# Bv_Switch.net
KiCad netlist of a schematic drawn in EAGLE
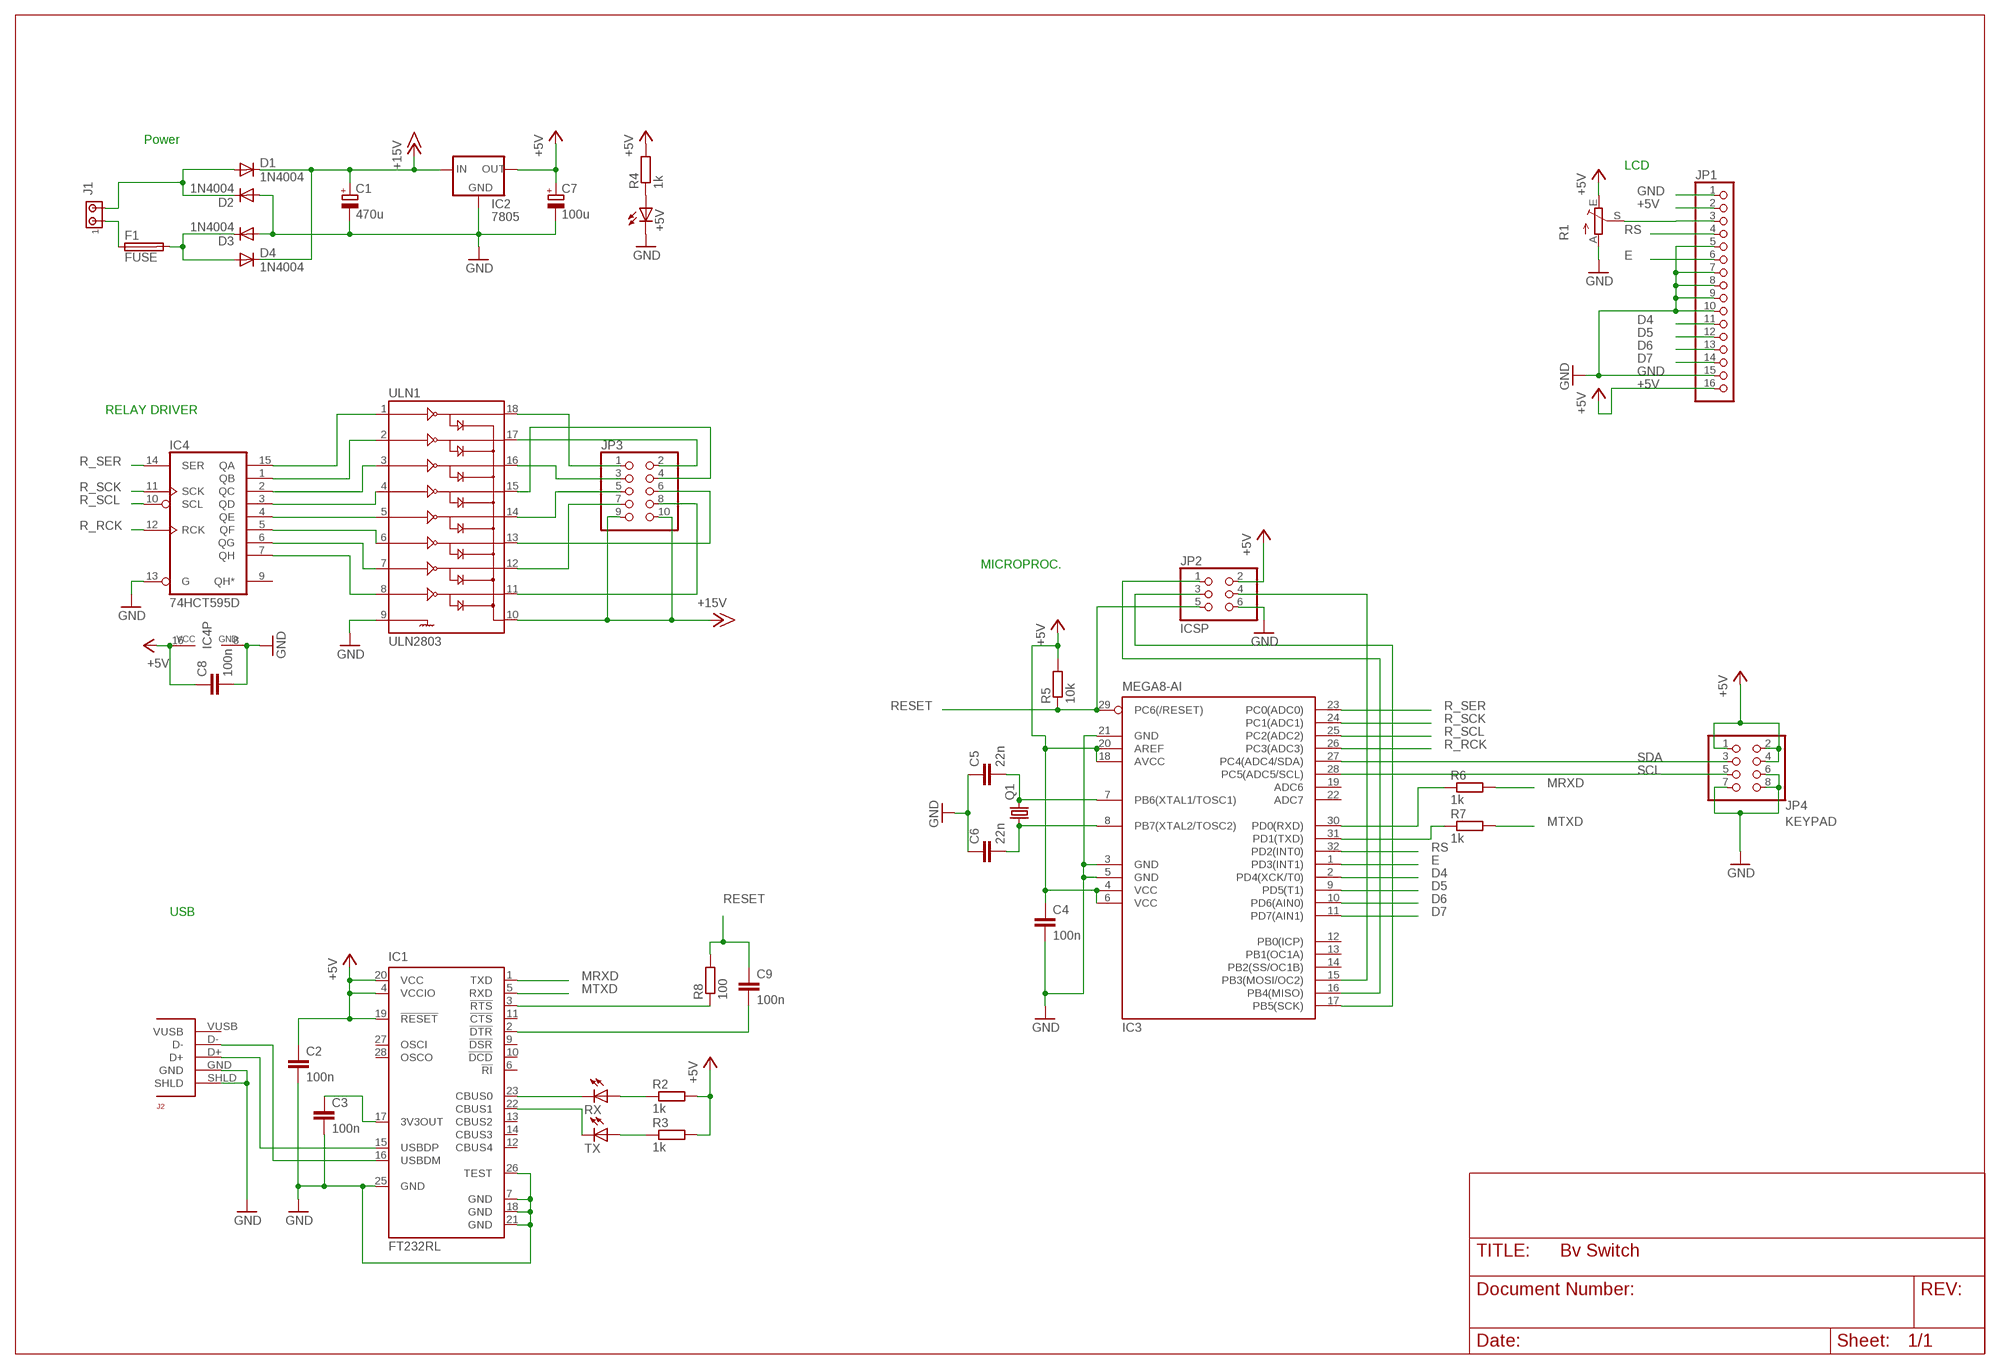
[diagram p0: schematic, sheet 1]

(export (version "E")
  (design (tool "Eeschema 10.0.6"))
  (components
    (comp (ref "+5V")
      (value "LEDCHIPLED_1206")
      (footprint "eagle-import:CHIPLED_1206")
      (libsource (lib "eagle-import") (part "LEDCHIPLED_1206"))
    )
    (comp (ref "C1")
      (value "470u")
      (footprint "eagle-import:153CLV-1010")
      (libsource (lib "eagle-import") (part "CPOL-EU153CLV-1010"))
    )
    (comp (ref "C2")
      (value "100n")
      (footprint "eagle-import:C1206")
      (libsource (lib "eagle-import") (part "C-EUC1206"))
    )
    (comp (ref "C3")
      (value "100n")
      (footprint "eagle-import:C1206")
      (libsource (lib "eagle-import") (part "C-EUC1206"))
    )
    (comp (ref "C4")
      (value "100n")
      (footprint "eagle-import:C1206")
      (libsource (lib "eagle-import") (part "C-EUC1206"))
    )
    (comp (ref "C5")
      (value "22n")
      (footprint "eagle-import:C1206")
      (libsource (lib "eagle-import") (part "C-EUC1206"))
    )
    (comp (ref "C6")
      (value "22n")
      (footprint "eagle-import:C1206")
      (libsource (lib "eagle-import") (part "C-EUC1206"))
    )
    (comp (ref "C7")
      (value "100u")
      (footprint "eagle-import:153CLV-1010")
      (libsource (lib "eagle-import") (part "CPOL-EU153CLV-1010"))
    )
    (comp (ref "C8")
      (value "100n")
      (footprint "eagle-import:C1206")
      (libsource (lib "eagle-import") (part "C-EUC1206"))
    )
    (comp (ref "C9")
      (value "100n")
      (footprint "eagle-import:C1206")
      (libsource (lib "eagle-import") (part "C-EUC1206"))
    )
    (comp (ref "D1")
      (value "1N4004")
      (footprint "eagle-import:DO41-10")
      (libsource (lib "eagle-import") (part "1N4004"))
    )
    (comp (ref "D2")
      (value "1N4004")
      (footprint "eagle-import:DO41-10")
      (libsource (lib "eagle-import") (part "1N4004"))
    )
    (comp (ref "D3")
      (value "1N4004")
      (footprint "eagle-import:DO41-10")
      (libsource (lib "eagle-import") (part "1N4004"))
    )
    (comp (ref "D4")
      (value "1N4004")
      (footprint "eagle-import:DO41-10")
      (libsource (lib "eagle-import") (part "1N4004"))
    )
    (comp (ref "F1")
      (value "FUSE")
      (footprint "eagle-import:FUSE_HOLDER_5X20MM")
      (libsource (lib "eagle-import") (part "FUSEBLANK_5X20MM"))
    )
    (comp (ref "IC1")
      (value "FT232RL")
      (footprint "eagle-import:SSOP28")
      (libsource (lib "eagle-import") (part "FT232RL"))
    )
    (comp (ref "IC2")
      (value "7805")
      (footprint "eagle-import:78XXL")
      (libsource (lib "eagle-import") (part "78XXL"))
    )
    (comp (ref "IC3")
      (value "MEGA8-AI")
      (footprint "eagle-import:TQFP32-08")
      (fields (field (name "MPN") "ATMEGA8-16AU"))
      (libsource (lib "eagle-import") (part "MEGA8-AI"))
    )
    (comp (ref "IC4")
      (value "74HCT595D")
      (footprint "eagle-import:SO16")
      (libsource (lib "eagle-import") (part "74595DHCT"))
    )
    (comp (ref "J1")
      (value "MTA02-156")
      (footprint "eagle-import:1X2MTA")
      (libsource (lib "eagle-import") (part "MTA02-156"))
    )
    (comp (ref "J2")
      (value "USBHD")
      (footprint "eagle-import:PINHD4")
      (libsource (lib "eagle-import") (part "USBHD"))
    )
    (comp (ref "JP1")
      (value "PINHD-1X16")
      (footprint "eagle-import:1X16")
      (libsource (lib "eagle-import") (part "PINHD-1X16"))
    )
    (comp (ref "JP2")
      (value "ICSP")
      (footprint "eagle-import:2X03")
      (libsource (lib "eagle-import") (part "PINHD-2X3"))
    )
    (comp (ref "JP3")
      (value "PINHD-2X5")
      (footprint "eagle-import:2X05")
      (libsource (lib "eagle-import") (part "PINHD-2X5"))
    )
    (comp (ref "JP4")
      (value "KEYPAD")
      (footprint "eagle-import:2X04")
      (libsource (lib "eagle-import") (part "PINHD-2X4"))
    )
    (comp (ref "Q1")
      (value "CRYSTALSM49")
      (footprint "eagle-import:SM49")
      (libsource (lib "eagle-import") (part "CRYSTALSM49"))
    )
    (comp (ref "R1")
      (value "TRIM_EU-CA6V")
      (footprint "eagle-import:CA6V")
      (libsource (lib "eagle-import") (part "TRIM_EU-CA6V"))
    )
    (comp (ref "R2")
      (value "1k")
      (footprint "eagle-import:R1206")
      (libsource (lib "eagle-import") (part "R-EU_R1206"))
    )
    (comp (ref "R3")
      (value "1k")
      (footprint "eagle-import:R1206")
      (libsource (lib "eagle-import") (part "R-EU_R1206"))
    )
    (comp (ref "R4")
      (value "1k")
      (footprint "eagle-import:R1206")
      (libsource (lib "eagle-import") (part "R-EU_R1206"))
    )
    (comp (ref "R5")
      (value "10k")
      (footprint "eagle-import:R1206")
      (libsource (lib "eagle-import") (part "R-EU_R1206"))
    )
    (comp (ref "R6")
      (value "1k")
      (footprint "eagle-import:R1206")
      (libsource (lib "eagle-import") (part "R-EU_R1206"))
    )
    (comp (ref "R7")
      (value "1k")
      (footprint "eagle-import:R1206")
      (libsource (lib "eagle-import") (part "R-EU_R1206"))
    )
    (comp (ref "R8")
      (value "100")
      (footprint "eagle-import:R1206")
      (libsource (lib "eagle-import") (part "R-EU_R1206"))
    )
    (comp (ref "RX")
      (value "LEDCHIPLED_1206")
      (footprint "eagle-import:CHIPLED_1206")
      (libsource (lib "eagle-import") (part "LEDCHIPLED_1206"))
    )
    (comp (ref "TX")
      (value "LEDCHIPLED_1206")
      (footprint "eagle-import:CHIPLED_1206")
      (libsource (lib "eagle-import") (part "LEDCHIPLED_1206"))
    )
    (comp (ref "ULN1")
      (value "ULN2803")
      (footprint "eagle-import:SO018")
      (libsource (lib "eagle-import") (part "ULN2803SOIC"))
    )
  )
  (nets
    (net (code "1") (name "+5V") (class "Default")
      (node (ref "C2") (pin "1") (pinfunction "1_1") (pintype "passive"))
      (node (ref "C4") (pin "1") (pinfunction "1_1") (pintype "passive"))
      (node (ref "C7") (pin "+") (pinfunction "+_+") (pintype "passive"))
      (node (ref "C8") (pin "1") (pinfunction "1_1") (pintype "passive"))
      (node (ref "IC1") (pin "19") (pinfunction "~{RESET}_19") (pintype "input"))
      (node (ref "IC1") (pin "20") (pinfunction "VCC_20") (pintype "power_in"))
      (node (ref "IC1") (pin "4") (pinfunction "VCCIO_4") (pintype "power_in"))
      (node (ref "IC2") (pin "OUT") (pinfunction "OUT_OUT") (pintype "passive"))
      (node (ref "IC3") (pin "18") (pinfunction "AVCC_18") (pintype "power_in"))
      (node (ref "IC3") (pin "20") (pinfunction "AREF_20") (pintype "passive"))
      (node (ref "IC3") (pin "4") (pinfunction "VCC_4") (pintype "power_in"))
      (node (ref "IC3") (pin "6") (pinfunction "VCC_6") (pintype "power_in"))
      (node (ref "IC4") (pin "16") (pinfunction "VCC_16") (pintype "power_in"))
      (node (ref "JP1") (pin "16") (pinfunction "16_16") (pintype "passive"))
      (node (ref "JP1") (pin "2") (pinfunction "2_2") (pintype "passive"))
      (node (ref "JP2") (pin "2") (pinfunction "2_2") (pintype "passive"))
      (node (ref "JP4") (pin "1") (pinfunction "1_1") (pintype "passive"))
      (node (ref "JP4") (pin "2") (pinfunction "2_2") (pintype "passive"))
      (node (ref "JP4") (pin "4") (pinfunction "4_4") (pintype "passive"))
      (node (ref "R1") (pin "E") (pinfunction "E_E") (pintype "passive"))
      (node (ref "R2") (pin "2") (pinfunction "2_2") (pintype "passive"))
      (node (ref "R3") (pin "2") (pinfunction "2_2") (pintype "passive"))
      (node (ref "R4") (pin "2") (pinfunction "2_2") (pintype "passive"))
      (node (ref "R5") (pin "2") (pinfunction "2_2") (pintype "passive"))
    )
    (net (code "2") (name "+15V") (class "Default")
      (node (ref "C1") (pin "+") (pinfunction "+_+") (pintype "passive"))
      (node (ref "D1") (pin "C") (pinfunction "C_C") (pintype "passive"))
      (node (ref "D4") (pin "C") (pinfunction "C_C") (pintype "passive"))
      (node (ref "IC2") (pin "IN") (pinfunction "IN_IN") (pintype "input"))
      (node (ref "JP3") (pin "10") (pinfunction "10_10") (pintype "passive"))
      (node (ref "JP3") (pin "9") (pinfunction "9_9") (pintype "passive"))
      (node (ref "ULN1") (pin "10") (pinfunction "10_10") (pintype "bidirectional"))
    )
    (net (code "3") (name "/D4") (class "Default")
      (node (ref "IC3") (pin "2") (pinfunction "PD4(XCK/T0)_2") (pintype "bidirectional"))
      (node (ref "JP1") (pin "11") (pinfunction "11_11") (pintype "passive"))
    )
    (net (code "4") (name "/D5") (class "Default")
      (node (ref "IC3") (pin "9") (pinfunction "PD5(T1)_9") (pintype "bidirectional"))
      (node (ref "JP1") (pin "12") (pinfunction "12_12") (pintype "passive"))
    )
    (net (code "5") (name "/D6") (class "Default")
      (node (ref "IC3") (pin "10") (pinfunction "PD6(AIN0)_10") (pintype "bidirectional"))
      (node (ref "JP1") (pin "13") (pinfunction "13_13") (pintype "passive"))
    )
    (net (code "6") (name "/D7") (class "Default")
      (node (ref "IC3") (pin "11") (pinfunction "PD7(AIN1)_11") (pintype "bidirectional"))
      (node (ref "JP1") (pin "14") (pinfunction "14_14") (pintype "passive"))
    )
    (net (code "7") (name "/E") (class "Default")
      (node (ref "IC3") (pin "1") (pinfunction "PD3(INT1)_1") (pintype "bidirectional"))
      (node (ref "JP1") (pin "6") (pinfunction "6_6") (pintype "passive"))
    )
    (net (code "8") (name "/MRXD") (class "Default")
      (node (ref "IC1") (pin "1") (pinfunction "TXD_1") (pintype "output"))
      (node (ref "R6") (pin "2") (pinfunction "2_2") (pintype "passive"))
    )
    (net (code "9") (name "/MTXD") (class "Default")
      (node (ref "IC1") (pin "5") (pinfunction "RXD_5") (pintype "input"))
      (node (ref "R7") (pin "2") (pinfunction "2_2") (pintype "passive"))
    )
    (net (code "10") (name "/RESET") (class "Default")
      (node (ref "C9") (pin "1") (pinfunction "1_1") (pintype "passive"))
      (node (ref "IC3") (pin "29") (pinfunction "PC6(/RESET)_29") (pintype "bidirectional"))
      (node (ref "JP2") (pin "5") (pinfunction "5_5") (pintype "passive"))
      (node (ref "R5") (pin "1") (pinfunction "1_1") (pintype "passive"))
      (node (ref "R8") (pin "2") (pinfunction "2_2") (pintype "passive"))
    )
    (net (code "11") (name "/RS") (class "Default")
      (node (ref "IC3") (pin "32") (pinfunction "PD2(INT0)_32") (pintype "bidirectional"))
      (node (ref "JP1") (pin "4") (pinfunction "4_4") (pintype "passive"))
    )
    (net (code "12") (name "/R_RCK") (class "Default")
      (node (ref "IC3") (pin "26") (pinfunction "PC3(ADC3)_26") (pintype "bidirectional"))
      (node (ref "IC4") (pin "12") (pinfunction "RCK_12") (pintype "input"))
    )
    (net (code "13") (name "/R_SCK") (class "Default")
      (node (ref "IC3") (pin "24") (pinfunction "PC1(ADC1)_24") (pintype "bidirectional"))
      (node (ref "IC4") (pin "11") (pinfunction "SCK_11") (pintype "input"))
    )
    (net (code "14") (name "/R_SCL") (class "Default")
      (node (ref "IC3") (pin "25") (pinfunction "PC2(ADC2)_25") (pintype "bidirectional"))
      (node (ref "IC4") (pin "10") (pinfunction "SCL_10") (pintype "input"))
    )
    (net (code "15") (name "/R_SER") (class "Default")
      (node (ref "IC3") (pin "23") (pinfunction "PC0(ADC0)_23") (pintype "bidirectional"))
      (node (ref "IC4") (pin "14") (pinfunction "SER_14") (pintype "input"))
    )
    (net (code "16") (name "/SCL") (class "Default")
      (node (ref "IC3") (pin "28") (pinfunction "PC5(ADC5/SCL)_28") (pintype "bidirectional"))
      (node (ref "JP4") (pin "5") (pinfunction "5_5") (pintype "passive"))
    )
    (net (code "17") (name "/SDA") (class "Default")
      (node (ref "IC3") (pin "27") (pinfunction "PC4(ADC4/SDA)_27") (pintype "bidirectional"))
      (node (ref "JP4") (pin "3") (pinfunction "3_3") (pintype "passive"))
    )
    (net (code "18") (name "GND") (class "Default")
      (node (ref "+5V") (pin "C") (pinfunction "C_C") (pintype "passive"))
      (node (ref "C1") (pin "-") (pinfunction "-_-") (pintype "passive"))
      (node (ref "C2") (pin "2") (pinfunction "2_2") (pintype "passive"))
      (node (ref "C3") (pin "2") (pinfunction "2_2") (pintype "passive"))
      (node (ref "C4") (pin "2") (pinfunction "2_2") (pintype "passive"))
      (node (ref "C5") (pin "1") (pinfunction "1_1") (pintype "passive"))
      (node (ref "C6") (pin "1") (pinfunction "1_1") (pintype "passive"))
      (node (ref "C7") (pin "-") (pinfunction "-_-") (pintype "passive"))
      (node (ref "C8") (pin "2") (pinfunction "2_2") (pintype "passive"))
      (node (ref "D2") (pin "A") (pinfunction "A_A") (pintype "passive"))
      (node (ref "D3") (pin "A") (pinfunction "A_A") (pintype "passive"))
      (node (ref "IC1") (pin "18") (pinfunction "GND_18") (pintype "power_in"))
      (node (ref "IC1") (pin "21") (pinfunction "GND_21") (pintype "power_in"))
      (node (ref "IC1") (pin "25") (pinfunction "GND_25") (pintype "power_in"))
      (node (ref "IC1") (pin "26") (pinfunction "TEST_26") (pintype "input"))
      (node (ref "IC1") (pin "7") (pinfunction "GND_7") (pintype "power_in"))
      (node (ref "IC2") (pin "GND") (pinfunction "GND_GND") (pintype "input"))
      (node (ref "IC3") (pin "21") (pinfunction "GND_21") (pintype "power_in"))
      (node (ref "IC3") (pin "3") (pinfunction "GND_3") (pintype "power_in"))
      (node (ref "IC3") (pin "5") (pinfunction "GND_5") (pintype "power_in"))
      (node (ref "IC4") (pin "13") (pinfunction "G_13") (pintype "input"))
      (node (ref "IC4") (pin "8") (pinfunction "GND_8") (pintype "power_in"))
      (node (ref "J2") (pin "GND") (pinfunction "GND_GND") (pintype "bidirectional"))
      (node (ref "J2") (pin "SHLD") (pinfunction "SHLD_SHLD") (pintype "bidirectional"))
      (node (ref "JP1") (pin "1") (pinfunction "1_1") (pintype "passive"))
      (node (ref "JP1") (pin "10") (pinfunction "10_10") (pintype "passive"))
      (node (ref "JP1") (pin "15") (pinfunction "15_15") (pintype "passive"))
      (node (ref "JP1") (pin "5") (pinfunction "5_5") (pintype "passive"))
      (node (ref "JP1") (pin "7") (pinfunction "7_7") (pintype "passive"))
      (node (ref "JP1") (pin "8") (pinfunction "8_8") (pintype "passive"))
      (node (ref "JP1") (pin "9") (pinfunction "9_9") (pintype "passive"))
      (node (ref "JP2") (pin "6") (pinfunction "6_6") (pintype "passive"))
      (node (ref "JP4") (pin "6") (pinfunction "6_6") (pintype "passive"))
      (node (ref "JP4") (pin "7") (pinfunction "7_7") (pintype "passive"))
      (node (ref "JP4") (pin "8") (pinfunction "8_8") (pintype "passive"))
      (node (ref "R1") (pin "A") (pinfunction "A_A") (pintype "passive"))
      (node (ref "ULN1") (pin "9") (pinfunction "9_9") (pintype "bidirectional"))
    )
    (net (code "19") (name "Net-(+5V-PadA)") (class "Default")
      (node (ref "+5V") (pin "A") (pinfunction "A_A") (pintype "passive"))
      (node (ref "R4") (pin "1") (pinfunction "1_1") (pintype "passive"))
    )
    (net (code "20") (name "Net-(D1-PadA)") (class "Default")
      (node (ref "D1") (pin "A") (pinfunction "A_A") (pintype "passive"))
      (node (ref "D2") (pin "C") (pinfunction "C_C") (pintype "passive"))
      (node (ref "J1") (pin "2") (pinfunction "2_2") (pintype "passive"))
    )
    (net (code "21") (name "Net-(D3-PadC)") (class "Default")
      (node (ref "D3") (pin "C") (pinfunction "C_C") (pintype "passive"))
      (node (ref "D4") (pin "A") (pinfunction "A_A") (pintype "passive"))
      (node (ref "F1") (pin "2") (pinfunction "2_2") (pintype "passive"))
    )
    (net (code "22") (name "Net-(F1-Pad1)") (class "Default")
      (node (ref "F1") (pin "1") (pinfunction "1_1") (pintype "passive"))
      (node (ref "J1") (pin "1") (pinfunction "1_1") (pintype "passive"))
    )
    (net (code "23") (name "Net-(IC1-3V3OUT)") (class "Default")
      (node (ref "C3") (pin "1") (pinfunction "1_1") (pintype "passive"))
      (node (ref "IC1") (pin "17") (pinfunction "3V3OUT_17") (pintype "output"))
    )
    (net (code "24") (name "Net-(IC1-CBUS0)") (class "Default")
      (node (ref "IC1") (pin "23") (pinfunction "CBUS0_23") (pintype "bidirectional"))
      (node (ref "RX") (pin "C") (pinfunction "C_C") (pintype "passive"))
    )
    (net (code "25") (name "Net-(IC1-CBUS1)") (class "Default")
      (node (ref "IC1") (pin "22") (pinfunction "CBUS1_22") (pintype "bidirectional"))
      (node (ref "TX") (pin "C") (pinfunction "C_C") (pintype "passive"))
    )
    (net (code "26") (name "Net-(IC1-USBDM)") (class "Default")
      (node (ref "IC1") (pin "16") (pinfunction "USBDM_16") (pintype "bidirectional"))
      (node (ref "J2") (pin "D-") (pinfunction "D-_D-") (pintype "bidirectional"))
    )
    (net (code "27") (name "Net-(IC1-USBDP)") (class "Default")
      (node (ref "IC1") (pin "15") (pinfunction "USBDP_15") (pintype "bidirectional"))
      (node (ref "J2") (pin "D+") (pinfunction "D+_D+") (pintype "bidirectional"))
    )
    (net (code "28") (name "Net-(IC1-~{DTR})") (class "Default")
      (node (ref "C9") (pin "2") (pinfunction "2_2") (pintype "passive"))
      (node (ref "IC1") (pin "2") (pinfunction "~{DTR}_2") (pintype "output"))
    )
    (net (code "29") (name "Net-(IC1-~{RTS})") (class "Default")
      (node (ref "IC1") (pin "3") (pinfunction "~{RTS}_3") (pintype "output"))
      (node (ref "R8") (pin "1") (pinfunction "1_1") (pintype "passive"))
    )
    (net (code "30") (name "Net-(IC3-PB3(MOSI{slash}OC2))") (class "Default")
      (node (ref "IC3") (pin "15") (pinfunction "PB3(MOSI/OC2)_15") (pintype "bidirectional"))
      (node (ref "JP2") (pin "4") (pinfunction "4_4") (pintype "passive"))
    )
    (net (code "31") (name "Net-(IC3-PB4(MISO))") (class "Default")
      (node (ref "IC3") (pin "16") (pinfunction "PB4(MISO)_16") (pintype "bidirectional"))
      (node (ref "JP2") (pin "1") (pinfunction "1_1") (pintype "passive"))
    )
    (net (code "32") (name "Net-(IC3-PB5(SCK))") (class "Default")
      (node (ref "IC3") (pin "17") (pinfunction "PB5(SCK)_17") (pintype "bidirectional"))
      (node (ref "JP2") (pin "3") (pinfunction "3_3") (pintype "passive"))
    )
    (net (code "33") (name "Net-(IC3-PB6(XTAL1{slash}TOSC1))") (class "Default")
      (node (ref "C5") (pin "2") (pinfunction "2_2") (pintype "passive"))
      (node (ref "IC3") (pin "7") (pinfunction "PB6(XTAL1/TOSC1)_7") (pintype "bidirectional"))
      (node (ref "Q1") (pin "2") (pinfunction "2_2") (pintype "passive"))
    )
    (net (code "34") (name "Net-(IC3-PB7(XTAL2{slash}TOSC2))") (class "Default")
      (node (ref "C6") (pin "2") (pinfunction "2_2") (pintype "passive"))
      (node (ref "IC3") (pin "8") (pinfunction "PB7(XTAL2/TOSC2)_8") (pintype "bidirectional"))
      (node (ref "Q1") (pin "1") (pinfunction "1_1") (pintype "passive"))
    )
    (net (code "35") (name "Net-(IC3-PD0(RXD))") (class "Default")
      (node (ref "IC3") (pin "30") (pinfunction "PD0(RXD)_30") (pintype "bidirectional"))
      (node (ref "R6") (pin "1") (pinfunction "1_1") (pintype "passive"))
    )
    (net (code "36") (name "Net-(IC3-PD1(TXD))") (class "Default")
      (node (ref "IC3") (pin "31") (pinfunction "PD1(TXD)_31") (pintype "bidirectional"))
      (node (ref "R7") (pin "1") (pinfunction "1_1") (pintype "passive"))
    )
    (net (code "37") (name "Net-(IC4A-QA)") (class "Default")
      (node (ref "IC4") (pin "15") (pinfunction "QA_15") (pintype "tri_state"))
      (node (ref "ULN1") (pin "1") (pinfunction "1_1") (pintype "bidirectional"))
    )
    (net (code "38") (name "Net-(IC4A-QB)") (class "Default")
      (node (ref "IC4") (pin "1") (pinfunction "QB_1") (pintype "tri_state"))
      (node (ref "ULN1") (pin "2") (pinfunction "2_2") (pintype "bidirectional"))
    )
    (net (code "39") (name "Net-(IC4A-QC)") (class "Default")
      (node (ref "IC4") (pin "2") (pinfunction "QC_2") (pintype "tri_state"))
      (node (ref "ULN1") (pin "3") (pinfunction "3_3") (pintype "bidirectional"))
    )
    (net (code "40") (name "Net-(IC4A-QD)") (class "Default")
      (node (ref "IC4") (pin "3") (pinfunction "QD_3") (pintype "tri_state"))
      (node (ref "ULN1") (pin "4") (pinfunction "4_4") (pintype "bidirectional"))
    )
    (net (code "41") (name "Net-(IC4A-QE)") (class "Default")
      (node (ref "IC4") (pin "4") (pinfunction "QE_4") (pintype "tri_state"))
      (node (ref "ULN1") (pin "5") (pinfunction "5_5") (pintype "bidirectional"))
    )
    (net (code "42") (name "Net-(IC4A-QF)") (class "Default")
      (node (ref "IC4") (pin "5") (pinfunction "QF_5") (pintype "tri_state"))
      (node (ref "ULN1") (pin "6") (pinfunction "6_6") (pintype "bidirectional"))
    )
    (net (code "43") (name "Net-(IC4A-QG)") (class "Default")
      (node (ref "IC4") (pin "6") (pinfunction "QG_6") (pintype "tri_state"))
      (node (ref "ULN1") (pin "7") (pinfunction "7_7") (pintype "bidirectional"))
    )
    (net (code "44") (name "Net-(IC4A-QH)") (class "Default")
      (node (ref "IC4") (pin "7") (pinfunction "QH_7") (pintype "tri_state"))
      (node (ref "ULN1") (pin "8") (pinfunction "8_8") (pintype "bidirectional"))
    )
    (net (code "45") (name "Net-(JP1-Pad3)") (class "Default")
      (node (ref "JP1") (pin "3") (pinfunction "3_3") (pintype "passive"))
      (node (ref "R1") (pin "S") (pinfunction "S_S") (pintype "passive"))
    )
    (net (code "46") (name "Net-(JP3-Pad1)") (class "Default")
      (node (ref "JP3") (pin "1") (pinfunction "1_1") (pintype "passive"))
      (node (ref "ULN1") (pin "18") (pinfunction "18_18") (pintype "bidirectional"))
    )
    (net (code "47") (name "Net-(JP3-Pad2)") (class "Default")
      (node (ref "JP3") (pin "2") (pinfunction "2_2") (pintype "passive"))
      (node (ref "ULN1") (pin "17") (pinfunction "17_17") (pintype "bidirectional"))
    )
    (net (code "48") (name "Net-(JP3-Pad3)") (class "Default")
      (node (ref "JP3") (pin "3") (pinfunction "3_3") (pintype "passive"))
      (node (ref "ULN1") (pin "16") (pinfunction "16_16") (pintype "bidirectional"))
    )
    (net (code "49") (name "Net-(JP3-Pad4)") (class "Default")
      (node (ref "JP3") (pin "4") (pinfunction "4_4") (pintype "passive"))
      (node (ref "ULN1") (pin "15") (pinfunction "15_15") (pintype "bidirectional"))
    )
    (net (code "50") (name "Net-(JP3-Pad5)") (class "Default")
      (node (ref "JP3") (pin "5") (pinfunction "5_5") (pintype "passive"))
      (node (ref "ULN1") (pin "14") (pinfunction "14_14") (pintype "bidirectional"))
    )
    (net (code "51") (name "Net-(JP3-Pad6)") (class "Default")
      (node (ref "JP3") (pin "6") (pinfunction "6_6") (pintype "passive"))
      (node (ref "ULN1") (pin "13") (pinfunction "13_13") (pintype "bidirectional"))
    )
    (net (code "52") (name "Net-(JP3-Pad7)") (class "Default")
      (node (ref "JP3") (pin "7") (pinfunction "7_7") (pintype "passive"))
      (node (ref "ULN1") (pin "12") (pinfunction "12_12") (pintype "bidirectional"))
    )
    (net (code "53") (name "Net-(JP3-Pad8)") (class "Default")
      (node (ref "JP3") (pin "8") (pinfunction "8_8") (pintype "passive"))
      (node (ref "ULN1") (pin "11") (pinfunction "11_11") (pintype "bidirectional"))
    )
    (net (code "54") (name "Net-(R2-Pad1)") (class "Default")
      (node (ref "R2") (pin "1") (pinfunction "1_1") (pintype "passive"))
      (node (ref "RX") (pin "A") (pinfunction "A_A") (pintype "passive"))
    )
    (net (code "55") (name "Net-(R3-Pad1)") (class "Default")
      (node (ref "R3") (pin "1") (pinfunction "1_1") (pintype "passive"))
      (node (ref "TX") (pin "A") (pinfunction "A_A") (pintype "passive"))
    )
    (net (code "56") (name "unconnected-(IC1-CBUS2-Pad13)") (class "Default")
      (node (ref "IC1") (pin "13") (pinfunction "CBUS2_13") (pintype "bidirectional"))
    )
    (net (code "57") (name "unconnected-(IC1-CBUS3-Pad14)") (class "Default")
      (node (ref "IC1") (pin "14") (pinfunction "CBUS3_14") (pintype "bidirectional"))
    )
    (net (code "58") (name "unconnected-(IC1-CBUS4-Pad12)") (class "Default")
      (node (ref "IC1") (pin "12") (pinfunction "CBUS4_12") (pintype "bidirectional"))
    )
    (net (code "59") (name "unconnected-(IC1-OSCI-Pad27)") (class "Default")
      (node (ref "IC1") (pin "27") (pinfunction "OSCI_27") (pintype "input"))
    )
    (net (code "60") (name "unconnected-(IC1-OSCO-Pad28)") (class "Default")
      (node (ref "IC1") (pin "28") (pinfunction "OSCO_28") (pintype "output"))
    )
    (net (code "61") (name "unconnected-(IC1-~{CTS}-Pad11)") (class "Default")
      (node (ref "IC1") (pin "11") (pinfunction "~{CTS}_11") (pintype "input"))
    )
    (net (code "62") (name "unconnected-(IC1-~{DCD}-Pad10)") (class "Default")
      (node (ref "IC1") (pin "10") (pinfunction "~{DCD}_10") (pintype "input"))
    )
    (net (code "63") (name "unconnected-(IC1-~{DSR}-Pad9)") (class "Default")
      (node (ref "IC1") (pin "9") (pinfunction "~{DSR}_9") (pintype "input"))
    )
    (net (code "64") (name "unconnected-(IC1-~{RI}-Pad6)") (class "Default")
      (node (ref "IC1") (pin "6") (pinfunction "~{RI}_6") (pintype "input"))
    )
    (net (code "65") (name "unconnected-(IC3-ADC6-Pad19)") (class "Default")
      (node (ref "IC3") (pin "19") (pinfunction "ADC6_19") (pintype "bidirectional"))
    )
    (net (code "66") (name "unconnected-(IC3-ADC7-Pad22)") (class "Default")
      (node (ref "IC3") (pin "22") (pinfunction "ADC7_22") (pintype "bidirectional"))
    )
    (net (code "67") (name "unconnected-(IC3-PB0(ICP)-Pad12)") (class "Default")
      (node (ref "IC3") (pin "12") (pinfunction "PB0(ICP)_12") (pintype "bidirectional"))
    )
    (net (code "68") (name "unconnected-(IC3-PB1(OC1A)-Pad13)") (class "Default")
      (node (ref "IC3") (pin "13") (pinfunction "PB1(OC1A)_13") (pintype "bidirectional"))
    )
    (net (code "69") (name "unconnected-(IC3-PB2(SS{slash}OC1B)-Pad14)") (class "Default")
      (node (ref "IC3") (pin "14") (pinfunction "PB2(SS/OC1B)_14") (pintype "bidirectional"))
    )
    (net (code "70") (name "unconnected-(IC4A-QH*-Pad9)") (class "Default")
      (node (ref "IC4") (pin "9") (pinfunction "QH*_9") (pintype "tri_state"))
    )
    (net (code "71") (name "unconnected-(J2-PadVUSB)") (class "Default")
      (node (ref "J2") (pin "VUSB") (pinfunction "VUSB_VUSB") (pintype "bidirectional"))
    )
  )
)
